# mcu.net
KiCad netlist of a schematic drawn in Altium Designer
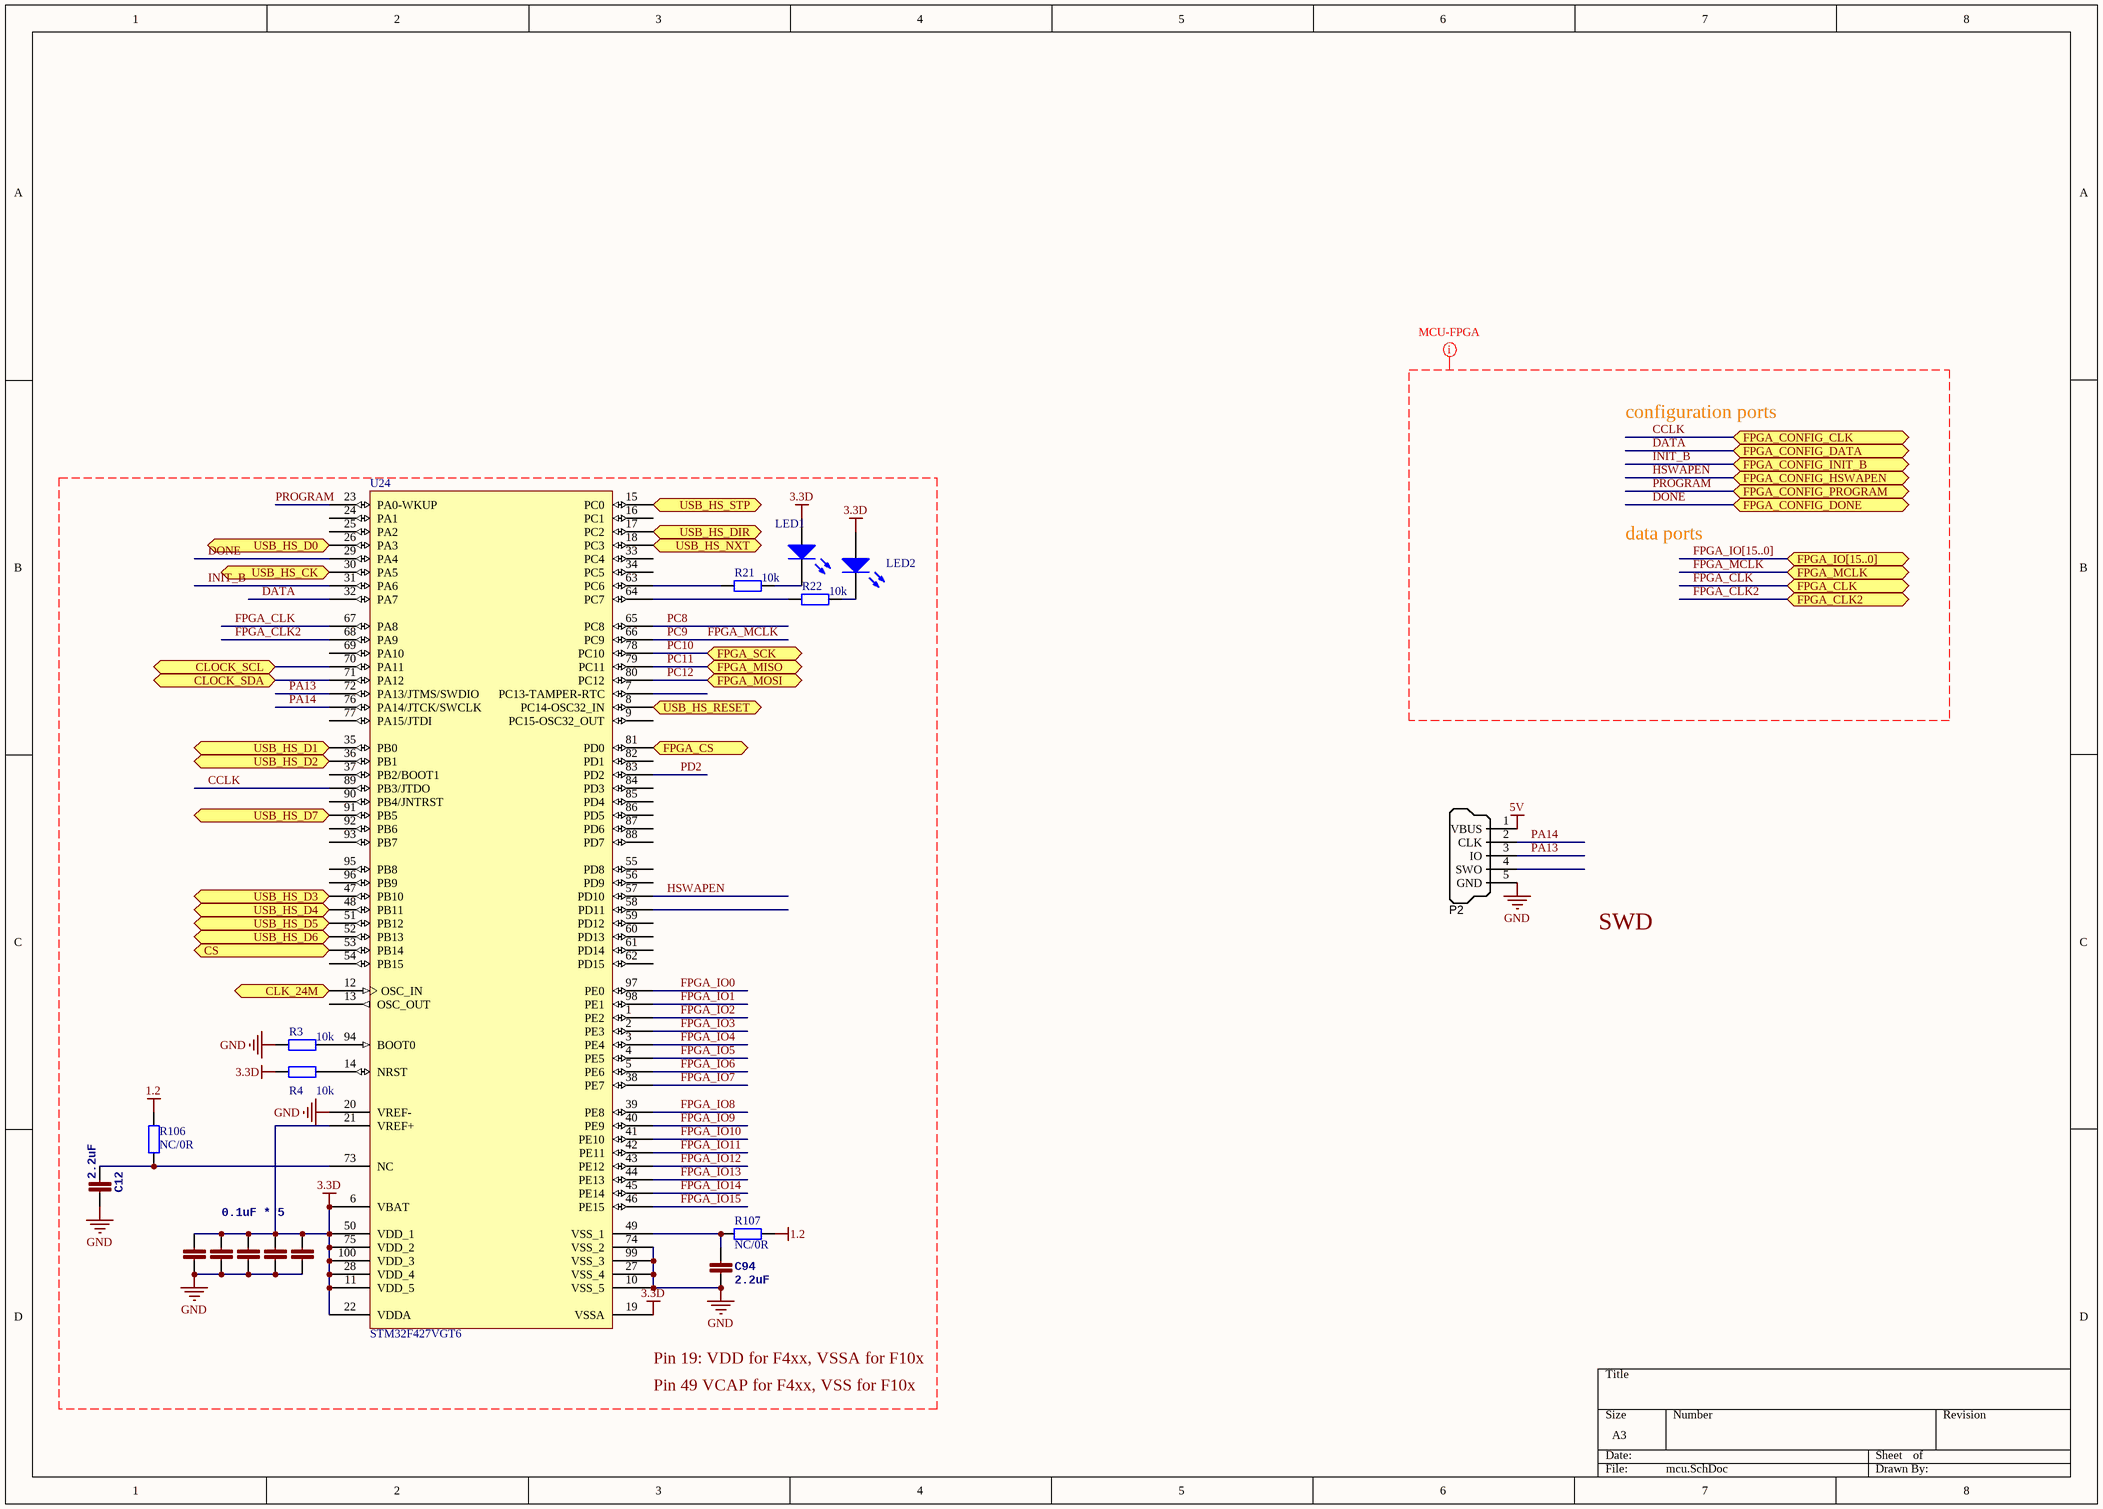
[diagram p0: mcu.SchDoc]

(export (version "E")
  (design (tool "Eeschema 10.0.6"))
  (components
    (comp (ref "C4")
      (value "0.1uF * 5")
      (footprint "0402")
      (description "<b>Capacitor</b>\nStandard 0603 ceramic capacitor, and 0.1\" leaded capacitor.")
      (fields (field (name "PARTNO") "CC0402ZRY5V7BB104"))
      (libsource (lib "*") (part "CAP0402-CAP"))
    )
    (comp (ref "C5")
      (value "1n")
      (footprint "0402")
      (description "<b>Capacitor</b>\nStandard 0603 ceramic capacitor, and 0.1\" leaded capacitor.")
      (fields (field (name "PARTNO") "CC0402ZRY5V7BB104"))
      (libsource (lib "pixhawk2") (part "CAP0402-CAP"))
    )
    (comp (ref "C6")
      (value "1n")
      (footprint "0402")
      (description "<b>Capacitor</b>\nStandard 0603 ceramic capacitor, and 0.1\" leaded capacitor.")
      (fields (field (name "PARTNO") "CC0402ZRY5V7BB104"))
      (libsource (lib "pixhawk2") (part "CAP0402-CAP"))
    )
    (comp (ref "C10")
      (value "1n")
      (footprint "0402")
      (description "<b>Capacitor</b>\nStandard 0603 ceramic capacitor, and 0.1\" leaded capacitor.")
      (fields (field (name "PARTNO") "CC0402ZRY5V7BB104"))
      (libsource (lib "pixhawk2") (part "CAP0402-CAP"))
    )
    (comp (ref "C12")
      (value "2.2uF")
      (footprint "0603")
      (description "<b>Capacitor</b>\nStandard 0603 ceramic capacitor, and 0.1\" leaded capacitor.")
      (fields (field (name "PARTNO") "CC0402ZRY5V7BB104"))
      (libsource (lib "pixhawk2") (part "CAP0402-CAP"))
    )
    (comp (ref "C25")
      (value "1n")
      (footprint "0402")
      (description "<b>Capacitor</b>\nStandard 0603 ceramic capacitor, and 0.1\" leaded capacitor.")
      (fields (field (name "PARTNO") "CC0402ZRY5V7BB104"))
      (libsource (lib "pixhawk2") (part "CAP0402-CAP"))
    )
    (comp (ref "C94")
      (value "2.2uF")
      (footprint "0603")
      (description "<b>Capacitor</b>\nStandard 0603 ceramic capacitor, and 0.1\" leaded capacitor.")
      (fields (field (name "PARTNO") "CC0402ZRY5V7BB104"))
      (libsource (lib "pixhawk2") (part "CAP0402-CAP"))
    )
    (comp (ref "LED1")
      (value "LED0")
      (footprint "0603")
      (description "Typical INFRARED GaAs LED")
      (fields (field (name "PUBLISHER") "Altium Limited"))
      (libsource (lib "Miscellaneous Devices") (part "LED0"))
    )
    (comp (ref "LED2")
      (value "LED0")
      (footprint "0603")
      (description "Typical INFRARED GaAs LED")
      (fields (field (name "PUBLISHER") "Altium Limited"))
      (libsource (lib "Miscellaneous Devices") (part "LED0"))
    )
    (comp (ref "P2")
      (value "SWD_MicroUSB")
      (footprint "MICRO-YZX")
      (description "Connector SMD USB Micro Type B middle mount")
      (libsource (lib "sch") (part "SWD_MicroUSB"))
    )
    (comp (ref "R3")
      (value "10k")
      (footprint "0402")
      (description "Resistor")
      (fields (field (name "PUBLISHER") "Altium Limited"))
      (libsource (lib "Miscellaneous Devices") (part "Res2"))
    )
    (comp (ref "R4")
      (value "10k")
      (footprint "0402")
      (description "Resistor")
      (fields (field (name "PUBLISHER") "Altium Limited"))
      (libsource (lib "") (part "Res2_1"))
    )
    (comp (ref "R21")
      (value "10k")
      (footprint "0402")
      (description "Resistor")
      (fields (field (name "PUBLISHER") "Altium Limited"))
      (libsource (lib "Miscellaneous Devices") (part "Res2"))
    )
    (comp (ref "R22")
      (value "10k")
      (footprint "0402")
      (description "Resistor")
      (fields (field (name "PUBLISHER") "Altium Limited"))
      (libsource (lib "Miscellaneous Devices") (part "Res2"))
    )
    (comp (ref "R106")
      (value "NC/0R")
      (footprint "0402")
      (description "Resistor")
      (fields (field (name "PUBLISHER") "Altium Limited"))
      (libsource (lib "") (part "Res2_2"))
    )
    (comp (ref "R107")
      (value "NC/0R")
      (footprint "0402")
      (description "Resistor")
      (fields (field (name "PUBLISHER") "Altium Limited"))
      (libsource (lib "") (part "Res2_1"))
    )
    (comp (ref "U24")
      (value "STM32F427VGT6")
      (footprint "LQFP100_N")
      (description "STM32 ARM-based 32-bit MCU with 64 Kbytes Flash, 100-pin LQFP, Industrial Temperature")
      (fields (field (name "PUBLISHER") "*"))
      (libsource (lib "ST Microcontroller 32-Bit STM32 SCH") (part "STM32F103VBT6"))
    )
  )
  (nets
    (net (code "1") (name "/CCLK") (class "Default")
      (node (ref "U24") (pin "89") (pinfunction "PB3/JTDO_89") (pintype "bidirectional"))
    )
    (net (code "2") (name "/CLK_24M") (class "Default")
      (node (ref "U24") (pin "12") (pinfunction "OSC_IN_12") (pintype "input"))
    )
    (net (code "3") (name "/CLOCK_SCL") (class "Default")
      (node (ref "U24") (pin "70") (pinfunction "PA11_70") (pintype "bidirectional"))
    )
    (net (code "4") (name "/CLOCK_SDA") (class "Default")
      (node (ref "U24") (pin "71") (pinfunction "PA12_71") (pintype "bidirectional"))
    )
    (net (code "5") (name "/CS") (class "Default")
      (node (ref "U24") (pin "53") (pinfunction "PB14_53") (pintype "bidirectional"))
    )
    (net (code "6") (name "/DATA") (class "Default")
      (node (ref "U24") (pin "32") (pinfunction "PA7_32") (pintype "bidirectional"))
    )
    (net (code "7") (name "/DONE") (class "Default")
      (node (ref "U24") (pin "29") (pinfunction "PA4_29") (pintype "bidirectional"))
    )
    (net (code "8") (name "/FPGA_CLK") (class "Default")
      (node (ref "U24") (pin "67") (pinfunction "PA8_67") (pintype "bidirectional"))
    )
    (net (code "9") (name "/FPGA_CLK2") (class "Default")
      (node (ref "U24") (pin "68") (pinfunction "PA9_68") (pintype "bidirectional"))
    )
    (net (code "10") (name "/FPGA_CS") (class "Default")
      (node (ref "U24") (pin "81") (pinfunction "PD0_81") (pintype "bidirectional"))
    )
    (net (code "11") (name "/FPGA_IO0") (class "Default")
      (node (ref "U24") (pin "97") (pinfunction "PE0_97") (pintype "bidirectional"))
    )
    (net (code "12") (name "/FPGA_IO1") (class "Default")
      (node (ref "U24") (pin "98") (pinfunction "PE1_98") (pintype "bidirectional"))
    )
    (net (code "13") (name "/FPGA_IO2") (class "Default")
      (node (ref "U24") (pin "1") (pinfunction "PE2_1") (pintype "bidirectional"))
    )
    (net (code "14") (name "/FPGA_IO3") (class "Default")
      (node (ref "U24") (pin "2") (pinfunction "PE3_2") (pintype "bidirectional"))
    )
    (net (code "15") (name "/FPGA_IO4") (class "Default")
      (node (ref "U24") (pin "3") (pinfunction "PE4_3") (pintype "bidirectional"))
    )
    (net (code "16") (name "/FPGA_IO5") (class "Default")
      (node (ref "U24") (pin "4") (pinfunction "PE5_4") (pintype "bidirectional"))
    )
    (net (code "17") (name "/FPGA_IO6") (class "Default")
      (node (ref "U24") (pin "5") (pinfunction "PE6_5") (pintype "bidirectional"))
    )
    (net (code "18") (name "/FPGA_IO7") (class "Default")
      (node (ref "U24") (pin "38") (pinfunction "PE7_38") (pintype "bidirectional"))
    )
    (net (code "19") (name "/FPGA_IO8") (class "Default")
      (node (ref "U24") (pin "39") (pinfunction "PE8_39") (pintype "bidirectional"))
    )
    (net (code "20") (name "/FPGA_IO9") (class "Default")
      (node (ref "U24") (pin "40") (pinfunction "PE9_40") (pintype "bidirectional"))
    )
    (net (code "21") (name "/FPGA_IO10") (class "Default")
      (node (ref "U24") (pin "41") (pinfunction "PE10_41") (pintype "bidirectional"))
    )
    (net (code "22") (name "/FPGA_IO11") (class "Default")
      (node (ref "U24") (pin "42") (pinfunction "PE11_42") (pintype "bidirectional"))
    )
    (net (code "23") (name "/FPGA_IO12") (class "Default")
      (node (ref "U24") (pin "43") (pinfunction "PE12_43") (pintype "bidirectional"))
    )
    (net (code "24") (name "/FPGA_IO13") (class "Default")
      (node (ref "U24") (pin "44") (pinfunction "PE13_44") (pintype "bidirectional"))
    )
    (net (code "25") (name "/FPGA_IO14") (class "Default")
      (node (ref "U24") (pin "45") (pinfunction "PE14_45") (pintype "bidirectional"))
    )
    (net (code "26") (name "/FPGA_IO15") (class "Default")
      (node (ref "U24") (pin "46") (pinfunction "PE15_46") (pintype "bidirectional"))
    )
    (net (code "28") (name "/FPGA_MCLK") (class "Default")
      (node (ref "U24") (pin "66") (pinfunction "PC9_66") (pintype "bidirectional"))
    )
    (net (code "29") (name "/HSWAPEN") (class "Default")
      (node (ref "U24") (pin "57") (pinfunction "PD10_57") (pintype "bidirectional"))
    )
    (net (code "30") (name "/INIT_B") (class "Default")
      (node (ref "U24") (pin "31") (pinfunction "PA6_31") (pintype "bidirectional"))
    )
    (net (code "31") (name "/PA13") (class "Default")
      (node (ref "P2") (pin "3") (pinfunction "IO_3") (pintype "passive"))
      (node (ref "U24") (pin "72") (pinfunction "PA13/JTMS/SWDIO_72") (pintype "bidirectional"))
    )
    (net (code "32") (name "/PA14") (class "Default")
      (node (ref "P2") (pin "2") (pinfunction "CLK_2") (pintype "passive"))
      (node (ref "U24") (pin "76") (pinfunction "PA14/JTCK/SWCLK_76") (pintype "bidirectional"))
    )
    (net (code "33") (name "/PC8") (class "Default")
      (node (ref "U24") (pin "65") (pinfunction "PC8_65") (pintype "bidirectional"))
    )
    (net (code "34") (name "/PC10") (class "Default")
      (node (ref "U24") (pin "78") (pinfunction "PC10_78") (pintype "bidirectional"))
    )
    (net (code "35") (name "/PC11") (class "Default")
      (node (ref "U24") (pin "79") (pinfunction "PC11_79") (pintype "bidirectional"))
    )
    (net (code "36") (name "/PC12") (class "Default")
      (node (ref "U24") (pin "80") (pinfunction "PC12_80") (pintype "bidirectional"))
    )
    (net (code "37") (name "/PD2") (class "Default")
      (node (ref "U24") (pin "83") (pinfunction "PD2_83") (pintype "bidirectional"))
    )
    (net (code "38") (name "/PROGRAM") (class "Default")
      (node (ref "U24") (pin "23") (pinfunction "PA0-WKUP_23") (pintype "bidirectional"))
    )
    (net (code "39") (name "/USB_HS_CK") (class "Default")
      (node (ref "U24") (pin "30") (pinfunction "PA5_30") (pintype "bidirectional"))
    )
    (net (code "40") (name "/USB_HS_D0") (class "Default")
      (node (ref "U24") (pin "26") (pinfunction "PA3_26") (pintype "bidirectional"))
    )
    (net (code "41") (name "/USB_HS_D1") (class "Default")
      (node (ref "U24") (pin "35") (pinfunction "PB0_35") (pintype "bidirectional"))
    )
    (net (code "42") (name "/USB_HS_D2") (class "Default")
      (node (ref "U24") (pin "36") (pinfunction "PB1_36") (pintype "bidirectional"))
    )
    (net (code "43") (name "/USB_HS_D3") (class "Default")
      (node (ref "U24") (pin "47") (pinfunction "PB10_47") (pintype "bidirectional"))
    )
    (net (code "44") (name "/USB_HS_D4") (class "Default")
      (node (ref "U24") (pin "48") (pinfunction "PB11_48") (pintype "bidirectional"))
    )
    (net (code "45") (name "/USB_HS_D5") (class "Default")
      (node (ref "U24") (pin "51") (pinfunction "PB12_51") (pintype "bidirectional"))
    )
    (net (code "46") (name "/USB_HS_D6") (class "Default")
      (node (ref "U24") (pin "52") (pinfunction "PB13_52") (pintype "bidirectional"))
    )
    (net (code "47") (name "/USB_HS_D7") (class "Default")
      (node (ref "U24") (pin "91") (pinfunction "PB5_91") (pintype "bidirectional"))
    )
    (net (code "48") (name "/USB_HS_DIR") (class "Default")
      (node (ref "U24") (pin "17") (pinfunction "PC2_17") (pintype "bidirectional"))
    )
    (net (code "49") (name "/USB_HS_NXT") (class "Default")
      (node (ref "U24") (pin "18") (pinfunction "PC3_18") (pintype "bidirectional"))
    )
    (net (code "50") (name "/USB_HS_RESET") (class "Default")
      (node (ref "U24") (pin "8") (pinfunction "PC14-OSC32_IN_8") (pintype "bidirectional"))
    )
    (net (code "51") (name "/USB_HS_STP") (class "Default")
      (node (ref "U24") (pin "15") (pinfunction "PC0_15") (pintype "bidirectional"))
    )
    (net (code "52") (name "1.2") (class "Default")
      (node (ref "R106") (pin "1") (pinfunction "1_1") (pintype "passive"))
      (node (ref "R107") (pin "1") (pinfunction "1_1") (pintype "passive"))
    )
    (net (code "53") (name "3.3D") (class "Default")
      (node (ref "C10") (pin "2") (pinfunction "2_2") (pintype "passive"))
      (node (ref "C25") (pin "2") (pinfunction "2_2") (pintype "passive"))
      (node (ref "C4") (pin "2") (pinfunction "2_2") (pintype "passive"))
      (node (ref "C5") (pin "2") (pinfunction "2_2") (pintype "passive"))
      (node (ref "C6") (pin "2") (pinfunction "2_2") (pintype "passive"))
      (node (ref "LED1") (pin "1") (pinfunction "A_1") (pintype "passive"))
      (node (ref "LED2") (pin "1") (pinfunction "A_1") (pintype "passive"))
      (node (ref "R4") (pin "2") (pinfunction "2_2") (pintype "passive"))
      (node (ref "U24") (pin "100") (pinfunction "VDD_3_100") (pintype "power_in"))
      (node (ref "U24") (pin "11") (pinfunction "VDD_5_11") (pintype "power_in"))
      (node (ref "U24") (pin "19") (pinfunction "VSSA_19") (pintype "power_in"))
      (node (ref "U24") (pin "21") (pinfunction "VREF+_21") (pintype "power_in"))
      (node (ref "U24") (pin "22") (pinfunction "VDDA_22") (pintype "power_in"))
      (node (ref "U24") (pin "28") (pinfunction "VDD_4_28") (pintype "power_in"))
      (node (ref "U24") (pin "50") (pinfunction "VDD_1_50") (pintype "power_in"))
      (node (ref "U24") (pin "6") (pinfunction "VBAT_6") (pintype "power_in"))
      (node (ref "U24") (pin "75") (pinfunction "VDD_2_75") (pintype "power_in"))
    )
    (net (code "54") (name "5V") (class "Default")
      (node (ref "P2") (pin "1") (pinfunction "VBUS_1") (pintype "passive"))
    )
    (net (code "55") (name "GND") (class "Default")
      (node (ref "C10") (pin "1") (pinfunction "1_1") (pintype "passive"))
      (node (ref "C12") (pin "1") (pinfunction "1_1") (pintype "passive"))
      (node (ref "C25") (pin "1") (pinfunction "1_1") (pintype "passive"))
      (node (ref "C4") (pin "1") (pinfunction "1_1") (pintype "passive"))
      (node (ref "C5") (pin "1") (pinfunction "1_1") (pintype "passive"))
      (node (ref "C6") (pin "1") (pinfunction "1_1") (pintype "passive"))
      (node (ref "C94") (pin "1") (pinfunction "1_1") (pintype "passive"))
      (node (ref "P2") (pin "5") (pinfunction "GND_5") (pintype "passive"))
      (node (ref "R3") (pin "1") (pinfunction "1_1") (pintype "passive"))
      (node (ref "U24") (pin "10") (pinfunction "VSS_5_10") (pintype "power_in"))
      (node (ref "U24") (pin "20") (pinfunction "VREF-_20") (pintype "power_in"))
      (node (ref "U24") (pin "27") (pinfunction "VSS_4_27") (pintype "power_in"))
      (node (ref "U24") (pin "74") (pinfunction "VSS_2_74") (pintype "power_in"))
      (node (ref "U24") (pin "99") (pinfunction "VSS_3_99") (pintype "power_in"))
    )
    (net (code "56") (name "Net-(LED1-K)") (class "Default")
      (node (ref "LED1") (pin "2") (pinfunction "K_2") (pintype "passive"))
      (node (ref "R21") (pin "2") (pinfunction "2_2") (pintype "passive"))
    )
    (net (code "57") (name "Net-(LED2-K)") (class "Default")
      (node (ref "LED2") (pin "2") (pinfunction "K_2") (pintype "passive"))
      (node (ref "R22") (pin "2") (pinfunction "2_2") (pintype "passive"))
    )
    (net (code "58") (name "Net-(U24-BOOT0)") (class "Default")
      (node (ref "R3") (pin "2") (pinfunction "2_2") (pintype "passive"))
      (node (ref "U24") (pin "94") (pinfunction "BOOT0_94") (pintype "input"))
    )
    (net (code "59") (name "Net-(U24-NC)") (class "Default")
      (node (ref "C12") (pin "2") (pinfunction "2_2") (pintype "passive"))
      (node (ref "R106") (pin "2") (pinfunction "2_2") (pintype "passive"))
      (node (ref "U24") (pin "73") (pinfunction "NC_73") (pintype "passive"))
    )
    (net (code "60") (name "Net-(U24-NRST)") (class "Default")
      (node (ref "R4") (pin "1") (pinfunction "1_1") (pintype "passive"))
      (node (ref "U24") (pin "14") (pinfunction "NRST_14") (pintype "bidirectional"))
    )
    (net (code "61") (name "Net-(U24-PC6)") (class "Default")
      (node (ref "R21") (pin "1") (pinfunction "1_1") (pintype "passive"))
      (node (ref "U24") (pin "63") (pinfunction "PC6_63") (pintype "bidirectional"))
    )
    (net (code "62") (name "Net-(U24-PC7)") (class "Default")
      (node (ref "R22") (pin "1") (pinfunction "1_1") (pintype "passive"))
      (node (ref "U24") (pin "64") (pinfunction "PC7_64") (pintype "bidirectional"))
    )
    (net (code "63") (name "Net-(U24-VSS_1)") (class "Default")
      (node (ref "C94") (pin "2") (pinfunction "2_2") (pintype "passive"))
      (node (ref "R107") (pin "2") (pinfunction "2_2") (pintype "passive"))
      (node (ref "U24") (pin "49") (pinfunction "VSS_1_49") (pintype "power_in"))
    )
    (net (code "64") (name "unconnected-(P2-SWO-Pad4)") (class "Default")
      (node (ref "P2") (pin "4") (pinfunction "SWO_4") (pintype "passive"))
    )
    (net (code "65") (name "unconnected-(U24-OSC_OUT-Pad13)") (class "Default")
      (node (ref "U24") (pin "13") (pinfunction "OSC_OUT_13") (pintype "output"))
    )
    (net (code "66") (name "unconnected-(U24-PA1-Pad24)") (class "Default")
      (node (ref "U24") (pin "24") (pinfunction "PA1_24") (pintype "bidirectional"))
    )
    (net (code "67") (name "unconnected-(U24-PA2-Pad25)") (class "Default")
      (node (ref "U24") (pin "25") (pinfunction "PA2_25") (pintype "bidirectional"))
    )
    (net (code "68") (name "unconnected-(U24-PA10-Pad69)") (class "Default")
      (node (ref "U24") (pin "69") (pinfunction "PA10_69") (pintype "bidirectional"))
    )
    (net (code "69") (name "unconnected-(U24-PA15{slash}JTDI-Pad77)") (class "Default")
      (node (ref "U24") (pin "77") (pinfunction "PA15/JTDI_77") (pintype "bidirectional"))
    )
    (net (code "70") (name "unconnected-(U24-PB2{slash}BOOT1-Pad37)") (class "Default")
      (node (ref "U24") (pin "37") (pinfunction "PB2/BOOT1_37") (pintype "bidirectional"))
    )
    (net (code "71") (name "unconnected-(U24-PB4{slash}JNTRST-Pad90)") (class "Default")
      (node (ref "U24") (pin "90") (pinfunction "PB4/JNTRST_90") (pintype "bidirectional"))
    )
    (net (code "72") (name "unconnected-(U24-PB6-Pad92)") (class "Default")
      (node (ref "U24") (pin "92") (pinfunction "PB6_92") (pintype "bidirectional"))
    )
    (net (code "73") (name "unconnected-(U24-PB7-Pad93)") (class "Default")
      (node (ref "U24") (pin "93") (pinfunction "PB7_93") (pintype "bidirectional"))
    )
    (net (code "74") (name "unconnected-(U24-PB8-Pad95)") (class "Default")
      (node (ref "U24") (pin "95") (pinfunction "PB8_95") (pintype "bidirectional"))
    )
    (net (code "75") (name "unconnected-(U24-PB9-Pad96)") (class "Default")
      (node (ref "U24") (pin "96") (pinfunction "PB9_96") (pintype "bidirectional"))
    )
    (net (code "76") (name "unconnected-(U24-PB15-Pad54)") (class "Default")
      (node (ref "U24") (pin "54") (pinfunction "PB15_54") (pintype "bidirectional"))
    )
    (net (code "77") (name "unconnected-(U24-PC1-Pad16)") (class "Default")
      (node (ref "U24") (pin "16") (pinfunction "PC1_16") (pintype "bidirectional"))
    )
    (net (code "78") (name "unconnected-(U24-PC4-Pad33)") (class "Default")
      (node (ref "U24") (pin "33") (pinfunction "PC4_33") (pintype "bidirectional"))
    )
    (net (code "79") (name "unconnected-(U24-PC5-Pad34)") (class "Default")
      (node (ref "U24") (pin "34") (pinfunction "PC5_34") (pintype "bidirectional"))
    )
    (net (code "80") (name "unconnected-(U24-PC13-TAMPER-RTC-Pad7)") (class "Default")
      (node (ref "U24") (pin "7") (pinfunction "PC13-TAMPER-RTC_7") (pintype "bidirectional"))
    )
    (net (code "81") (name "unconnected-(U24-PC15-OSC32_OUT-Pad9)") (class "Default")
      (node (ref "U24") (pin "9") (pinfunction "PC15-OSC32_OUT_9") (pintype "bidirectional"))
    )
    (net (code "82") (name "unconnected-(U24-PD1-Pad82)") (class "Default")
      (node (ref "U24") (pin "82") (pinfunction "PD1_82") (pintype "bidirectional"))
    )
    (net (code "83") (name "unconnected-(U24-PD3-Pad84)") (class "Default")
      (node (ref "U24") (pin "84") (pinfunction "PD3_84") (pintype "bidirectional"))
    )
    (net (code "84") (name "unconnected-(U24-PD4-Pad85)") (class "Default")
      (node (ref "U24") (pin "85") (pinfunction "PD4_85") (pintype "bidirectional"))
    )
    (net (code "85") (name "unconnected-(U24-PD5-Pad86)") (class "Default")
      (node (ref "U24") (pin "86") (pinfunction "PD5_86") (pintype "bidirectional"))
    )
    (net (code "86") (name "unconnected-(U24-PD6-Pad87)") (class "Default")
      (node (ref "U24") (pin "87") (pinfunction "PD6_87") (pintype "bidirectional"))
    )
    (net (code "87") (name "unconnected-(U24-PD7-Pad88)") (class "Default")
      (node (ref "U24") (pin "88") (pinfunction "PD7_88") (pintype "bidirectional"))
    )
    (net (code "88") (name "unconnected-(U24-PD8-Pad55)") (class "Default")
      (node (ref "U24") (pin "55") (pinfunction "PD8_55") (pintype "bidirectional"))
    )
    (net (code "89") (name "unconnected-(U24-PD9-Pad56)") (class "Default")
      (node (ref "U24") (pin "56") (pinfunction "PD9_56") (pintype "bidirectional"))
    )
    (net (code "90") (name "unconnected-(U24-PD11-Pad58)") (class "Default")
      (node (ref "U24") (pin "58") (pinfunction "PD11_58") (pintype "bidirectional"))
    )
    (net (code "91") (name "unconnected-(U24-PD12-Pad59)") (class "Default")
      (node (ref "U24") (pin "59") (pinfunction "PD12_59") (pintype "bidirectional"))
    )
    (net (code "92") (name "unconnected-(U24-PD13-Pad60)") (class "Default")
      (node (ref "U24") (pin "60") (pinfunction "PD13_60") (pintype "bidirectional"))
    )
    (net (code "93") (name "unconnected-(U24-PD14-Pad61)") (class "Default")
      (node (ref "U24") (pin "61") (pinfunction "PD14_61") (pintype "bidirectional"))
    )
    (net (code "94") (name "unconnected-(U24-PD15-Pad62)") (class "Default")
      (node (ref "U24") (pin "62") (pinfunction "PD15_62") (pintype "bidirectional"))
    )
  )
)
